# Arsatech-Vital-Tracker-PCB.net
KiCad netlist of a schematic drawn in EasyEDA Pro
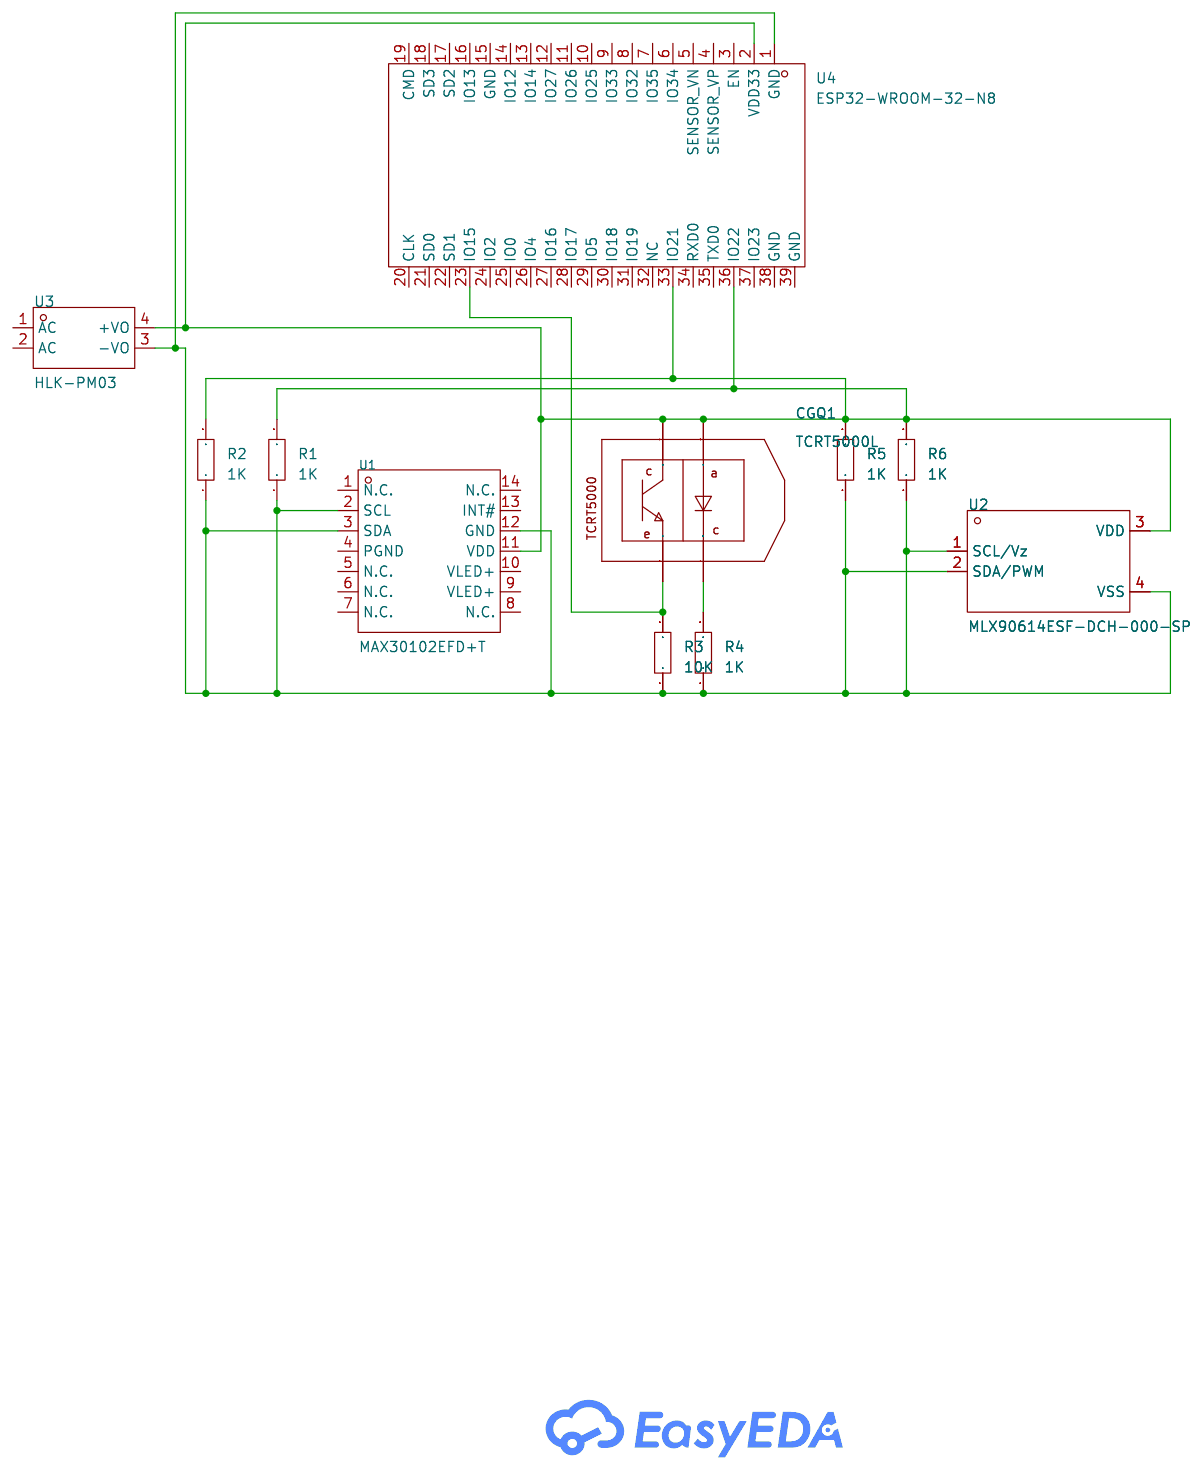
[diagram p0: schematic sheet]

(export (version "E")
  (design (tool "Eeschema 10.0.6"))
  (components
    (comp (ref "CGQ1")
      (value "TCRT5000L")
      (footprint "easyedapro:OPTO-TH_TCRT5000L")
      (fields (field (name "Manufacturer") "VISHAY(威世)"))
      (libsource (lib "easyedapro") (part "TCRT5000L"))
    )
    (comp (ref "R1") (value "1K") (footprint "easyedapro:R0603") (libsource (lib "easyedapro") (part "Res")))
    (comp (ref "R2") (value "1K") (footprint "easyedapro:R0603") (libsource (lib "easyedapro") (part "Res")))
    (comp (ref "R3") (value "10K") (footprint "easyedapro:R0603") (libsource (lib "easyedapro") (part "Res")))
    (comp (ref "R4") (value "1K") (footprint "easyedapro:R0603") (libsource (lib "easyedapro") (part "Res")))
    (comp (ref "R5") (value "1K") (footprint "easyedapro:R0603") (libsource (lib "easyedapro") (part "Res")))
    (comp (ref "R6") (value "1K") (footprint "easyedapro:R0603") (libsource (lib "easyedapro") (part "Res")))
    (comp (ref "U1")
      (value "MAX30102EFD+T")
      (footprint "easyedapro:OESIP-14_L5.6-W3.3-P0.80-TL")
      (description "Operating Temperature:-40°C~+85°C Operating Temperature:-40°C~+85°C")
      (fields (field (name "Manufacturer") "ADI(亚德诺)/MAXIM(美信)"))
      (libsource (lib "easyedapro") (part "MAX30102EFD+T_C6454833"))
    )
    (comp (ref "U2")
      (value "MLX90614ESF-DCH-000-SP")
      (footprint "easyedapro:TO-39-4_MELEXIS_MLX90614XXA")
      (description "Resolution:- Resolution:- Supply Voltage:2.6V~3.6V Supply Voltage:2.6V~3.6V")
      (fields (field (name "Manufacturer") "Melexis(比利时迈来芯)"))
      (libsource (lib "easyedapro") (part "MLX90614ESF-DCH-000-SP"))
    )
    (comp (ref "U3")
      (value "HLK-PM03")
      (footprint "easyedapro:PWRM-TH_HLK-PM03")
      (fields (field (name "Manufacturer") "HI-LINK(海凌科)"))
      (libsource (lib "easyedapro") (part "HLK-PM03"))
    )
    (comp (ref "U4")
      (value "ESP32-WROOM-32-N8")
      (footprint "easyedapro:WIFIM-SMD_39P-L25.5-W18.0-P1.27")
      (fields (field (name "Manufacturer") "ESPRESSIF(乐鑫)"))
      (libsource (lib "easyedapro") (part "ESP32-WROOM-32(8MB)"))
    )
  )
  (nets
    (net (code "1") (name "Net-(CGQ1-A)") (class "Default")
      (node (ref "CGQ1") (pin "1") (pinfunction "C_1") (pintype "unspecified"))
      (node (ref "CGQ1") (pin "3") (pinfunction "A_3") (pintype "unspecified"))
      (node (ref "R1") (pin "2") (pinfunction "2_2") (pintype "input"))
      (node (ref "R2") (pin "2") (pinfunction "2_2") (pintype "input"))
      (node (ref "R5") (pin "2") (pinfunction "2_2") (pintype "input"))
      (node (ref "R6") (pin "2") (pinfunction "2_2") (pintype "input"))
      (node (ref "U1") (pin "11") (pinfunction "VDD_11") (pintype "input"))
      (node (ref "U2") (pin "3") (pinfunction "VDD_3") (pintype "unspecified"))
      (node (ref "U3") (pin "4") (pinfunction "+VO_4") (pintype "unspecified"))
      (node (ref "U4") (pin "2") (pinfunction "VDD33_2") (pintype "unspecified"))
      (node (ref "U4") (pin "33") (pinfunction "IO21_33") (pintype "unspecified"))
      (node (ref "U4") (pin "36") (pinfunction "IO22_36") (pintype "unspecified"))
    )
    (net (code "2") (name "Net-(CGQ1-C-Pad4)") (class "Default")
      (node (ref "CGQ1") (pin "4") (pinfunction "C_4") (pintype "unspecified"))
      (node (ref "R4") (pin "2") (pinfunction "2_2") (pintype "input"))
    )
    (net (code "3") (name "Net-(CGQ1-E)") (class "Default")
      (node (ref "CGQ1") (pin "2") (pinfunction "E_2") (pintype "unspecified"))
      (node (ref "R3") (pin "2") (pinfunction "2_2") (pintype "input"))
      (node (ref "U4") (pin "23") (pinfunction "IO15_23") (pintype "unspecified"))
    )
    (net (code "4") (name "Net-(U1-GND)") (class "Default")
      (node (ref "R1") (pin "1") (pinfunction "1_1") (pintype "input"))
      (node (ref "R2") (pin "1") (pinfunction "1_1") (pintype "input"))
      (node (ref "R3") (pin "1") (pinfunction "1_1") (pintype "input"))
      (node (ref "R4") (pin "1") (pinfunction "1_1") (pintype "input"))
      (node (ref "R5") (pin "1") (pinfunction "1_1") (pintype "input"))
      (node (ref "R6") (pin "1") (pinfunction "1_1") (pintype "input"))
      (node (ref "U1") (pin "12") (pinfunction "GND_12") (pintype "input"))
      (node (ref "U1") (pin "2") (pinfunction "SCL_2") (pintype "input"))
      (node (ref "U1") (pin "3") (pinfunction "SDA_3") (pintype "input"))
      (node (ref "U2") (pin "1") (pinfunction "SCL/Vz_1") (pintype "unspecified"))
      (node (ref "U2") (pin "2") (pinfunction "SDA/PWM_2") (pintype "unspecified"))
      (node (ref "U2") (pin "4") (pinfunction "VSS_4") (pintype "unspecified"))
      (node (ref "U3") (pin "3") (pinfunction "-VO_3") (pintype "unspecified"))
      (node (ref "U4") (pin "1") (pinfunction "GND_1") (pintype "unspecified"))
    )
    (net (code "5") (name "unconnected-(U1-INT#-Pad13)") (class "Default")
      (node (ref "U1") (pin "13") (pinfunction "INT#_13") (pintype "input"))
    )
    (net (code "6") (name "unconnected-(U1-N.C.-Pad1)") (class "Default")
      (node (ref "U1") (pin "1") (pinfunction "N.C._1") (pintype "input"))
    )
    (net (code "7") (name "unconnected-(U1-N.C.-Pad5)") (class "Default")
      (node (ref "U1") (pin "5") (pinfunction "N.C._5") (pintype "input"))
    )
    (net (code "8") (name "unconnected-(U1-N.C.-Pad6)") (class "Default")
      (node (ref "U1") (pin "6") (pinfunction "N.C._6") (pintype "input"))
    )
    (net (code "9") (name "unconnected-(U1-N.C.-Pad7)") (class "Default")
      (node (ref "U1") (pin "7") (pinfunction "N.C._7") (pintype "input"))
    )
    (net (code "10") (name "unconnected-(U1-N.C.-Pad8)") (class "Default")
      (node (ref "U1") (pin "8") (pinfunction "N.C._8") (pintype "input"))
    )
    (net (code "11") (name "unconnected-(U1-N.C.-Pad14)") (class "Default")
      (node (ref "U1") (pin "14") (pinfunction "N.C._14") (pintype "input"))
    )
    (net (code "12") (name "unconnected-(U1-PGND-Pad4)") (class "Default")
      (node (ref "U1") (pin "4") (pinfunction "PGND_4") (pintype "input"))
    )
    (net (code "13") (name "unconnected-(U1-VLED+-Pad9)") (class "Default")
      (node (ref "U1") (pin "9") (pinfunction "VLED+_9") (pintype "input"))
    )
    (net (code "14") (name "unconnected-(U1-VLED+-Pad10)") (class "Default")
      (node (ref "U1") (pin "10") (pinfunction "VLED+_10") (pintype "input"))
    )
    (net (code "15") (name "unconnected-(U3-AC-Pad1)") (class "Default")
      (node (ref "U3") (pin "1") (pinfunction "AC_1") (pintype "unspecified"))
    )
    (net (code "16") (name "unconnected-(U3-AC-Pad2)") (class "Default")
      (node (ref "U3") (pin "2") (pinfunction "AC_2") (pintype "unspecified"))
    )
    (net (code "17") (name "unconnected-(U4-CLK-Pad20)") (class "Default")
      (node (ref "U4") (pin "20") (pinfunction "CLK_20") (pintype "unspecified"))
    )
    (net (code "18") (name "unconnected-(U4-CMD-Pad19)") (class "Default")
      (node (ref "U4") (pin "19") (pinfunction "CMD_19") (pintype "unspecified"))
    )
    (net (code "19") (name "unconnected-(U4-EN-Pad3)") (class "Default")
      (node (ref "U4") (pin "3") (pinfunction "EN_3") (pintype "unspecified"))
    )
    (net (code "20") (name "unconnected-(U4-GND-Pad15)") (class "Default")
      (node (ref "U4") (pin "15") (pinfunction "GND_15") (pintype "unspecified"))
    )
    (net (code "21") (name "unconnected-(U4-GND-Pad38)") (class "Default")
      (node (ref "U4") (pin "38") (pinfunction "GND_38") (pintype "unspecified"))
    )
    (net (code "22") (name "unconnected-(U4-GND-Pad39)") (class "Default")
      (node (ref "U4") (pin "39") (pinfunction "GND_39") (pintype "unspecified"))
    )
    (net (code "23") (name "unconnected-(U4-IO0-Pad25)") (class "Default")
      (node (ref "U4") (pin "25") (pinfunction "IO0_25") (pintype "unspecified"))
    )
    (net (code "24") (name "unconnected-(U4-IO2-Pad24)") (class "Default")
      (node (ref "U4") (pin "24") (pinfunction "IO2_24") (pintype "unspecified"))
    )
    (net (code "25") (name "unconnected-(U4-IO4-Pad26)") (class "Default")
      (node (ref "U4") (pin "26") (pinfunction "IO4_26") (pintype "unspecified"))
    )
    (net (code "26") (name "unconnected-(U4-IO5-Pad29)") (class "Default")
      (node (ref "U4") (pin "29") (pinfunction "IO5_29") (pintype "unspecified"))
    )
    (net (code "27") (name "unconnected-(U4-IO12-Pad14)") (class "Default")
      (node (ref "U4") (pin "14") (pinfunction "IO12_14") (pintype "unspecified"))
    )
    (net (code "28") (name "unconnected-(U4-IO13-Pad16)") (class "Default")
      (node (ref "U4") (pin "16") (pinfunction "IO13_16") (pintype "unspecified"))
    )
    (net (code "29") (name "unconnected-(U4-IO14-Pad13)") (class "Default")
      (node (ref "U4") (pin "13") (pinfunction "IO14_13") (pintype "unspecified"))
    )
    (net (code "30") (name "unconnected-(U4-IO16-Pad27)") (class "Default")
      (node (ref "U4") (pin "27") (pinfunction "IO16_27") (pintype "unspecified"))
    )
    (net (code "31") (name "unconnected-(U4-IO17-Pad28)") (class "Default")
      (node (ref "U4") (pin "28") (pinfunction "IO17_28") (pintype "unspecified"))
    )
    (net (code "32") (name "unconnected-(U4-IO18-Pad30)") (class "Default")
      (node (ref "U4") (pin "30") (pinfunction "IO18_30") (pintype "unspecified"))
    )
    (net (code "33") (name "unconnected-(U4-IO19-Pad31)") (class "Default")
      (node (ref "U4") (pin "31") (pinfunction "IO19_31") (pintype "unspecified"))
    )
    (net (code "34") (name "unconnected-(U4-IO23-Pad37)") (class "Default")
      (node (ref "U4") (pin "37") (pinfunction "IO23_37") (pintype "unspecified"))
    )
    (net (code "35") (name "unconnected-(U4-IO25-Pad10)") (class "Default")
      (node (ref "U4") (pin "10") (pinfunction "IO25_10") (pintype "unspecified"))
    )
    (net (code "36") (name "unconnected-(U4-IO26-Pad11)") (class "Default")
      (node (ref "U4") (pin "11") (pinfunction "IO26_11") (pintype "unspecified"))
    )
    (net (code "37") (name "unconnected-(U4-IO27-Pad12)") (class "Default")
      (node (ref "U4") (pin "12") (pinfunction "IO27_12") (pintype "unspecified"))
    )
    (net (code "38") (name "unconnected-(U4-IO32-Pad8)") (class "Default")
      (node (ref "U4") (pin "8") (pinfunction "IO32_8") (pintype "unspecified"))
    )
    (net (code "39") (name "unconnected-(U4-IO33-Pad9)") (class "Default")
      (node (ref "U4") (pin "9") (pinfunction "IO33_9") (pintype "unspecified"))
    )
    (net (code "40") (name "unconnected-(U4-IO34-Pad6)") (class "Default")
      (node (ref "U4") (pin "6") (pinfunction "IO34_6") (pintype "unspecified"))
    )
    (net (code "41") (name "unconnected-(U4-IO35-Pad7)") (class "Default")
      (node (ref "U4") (pin "7") (pinfunction "IO35_7") (pintype "unspecified"))
    )
    (net (code "42") (name "unconnected-(U4-NC-Pad32)") (class "Default")
      (node (ref "U4") (pin "32") (pinfunction "NC_32") (pintype "unspecified"))
    )
    (net (code "43") (name "unconnected-(U4-RXD0-Pad34)") (class "Default")
      (node (ref "U4") (pin "34") (pinfunction "RXD0_34") (pintype "unspecified"))
    )
    (net (code "44") (name "unconnected-(U4-SD0-Pad21)") (class "Default")
      (node (ref "U4") (pin "21") (pinfunction "SD0_21") (pintype "unspecified"))
    )
    (net (code "45") (name "unconnected-(U4-SD1-Pad22)") (class "Default")
      (node (ref "U4") (pin "22") (pinfunction "SD1_22") (pintype "unspecified"))
    )
    (net (code "46") (name "unconnected-(U4-SD2-Pad17)") (class "Default")
      (node (ref "U4") (pin "17") (pinfunction "SD2_17") (pintype "unspecified"))
    )
    (net (code "47") (name "unconnected-(U4-SD3-Pad18)") (class "Default")
      (node (ref "U4") (pin "18") (pinfunction "SD3_18") (pintype "unspecified"))
    )
    (net (code "48") (name "unconnected-(U4-SENSOR_VN-Pad5)") (class "Default")
      (node (ref "U4") (pin "5") (pinfunction "SENSOR_VN_5") (pintype "unspecified"))
    )
    (net (code "49") (name "unconnected-(U4-SENSOR_VP-Pad4)") (class "Default")
      (node (ref "U4") (pin "4") (pinfunction "SENSOR_VP_4") (pintype "unspecified"))
    )
    (net (code "50") (name "unconnected-(U4-TXD0-Pad35)") (class "Default")
      (node (ref "U4") (pin "35") (pinfunction "TXD0_35") (pintype "unspecified"))
    )
  )
)
